# temp.net
KiCad netlist of a schematic drawn in EAGLE
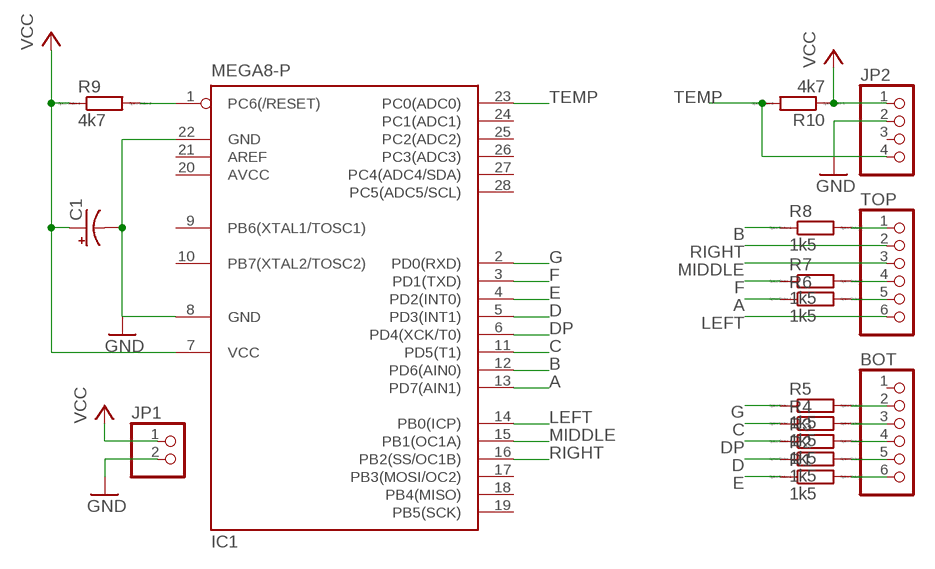
[diagram p0: schematic, sheet 1]

(export (version "E")
  (design (tool "Eeschema 10.0.6"))
  (components
    (comp (ref "BOT")
      (value "PINHD-1X6")
      (footprint "eagle-import:1X06")
      (libsource (lib "eagle-import") (part "PINHD-1X6"))
    )
    (comp (ref "C1")
      (value "CPOL-US153CLV-0505")
      (footprint "eagle-import:153CLV-0505")
      (libsource (lib "eagle-import") (part "CPOL-US153CLV-0505"))
    )
    (comp (ref "IC1")
      (value "MEGA8-P")
      (footprint "eagle-import:DIL28-3")
      (libsource (lib "eagle-import") (part "MEGA8-P"))
    )
    (comp (ref "JP1")
      (value "PINHD-1X2")
      (footprint "eagle-import:1X02")
      (libsource (lib "eagle-import") (part "PINHD-1X2"))
    )
    (comp (ref "JP2")
      (value "PINHD-1X4")
      (footprint "eagle-import:1X04")
      (libsource (lib "eagle-import") (part "PINHD-1X4"))
    )
    (comp (ref "R1")
      (value "1k5")
      (footprint "eagle-import:R1206")
      (libsource (lib "eagle-import") (part "R-EU_R1206"))
    )
    (comp (ref "R2")
      (value "1k5")
      (footprint "eagle-import:R1206")
      (libsource (lib "eagle-import") (part "R-EU_R1206"))
    )
    (comp (ref "R3")
      (value "1k5")
      (footprint "eagle-import:R1206")
      (libsource (lib "eagle-import") (part "R-EU_R1206"))
    )
    (comp (ref "R4")
      (value "1k5")
      (footprint "eagle-import:R1206")
      (libsource (lib "eagle-import") (part "R-EU_R1206"))
    )
    (comp (ref "R5")
      (value "1k5")
      (footprint "eagle-import:R1206")
      (libsource (lib "eagle-import") (part "R-EU_R1206"))
    )
    (comp (ref "R6")
      (value "1k5")
      (footprint "eagle-import:R1206")
      (libsource (lib "eagle-import") (part "R-EU_R1206"))
    )
    (comp (ref "R7")
      (value "1k5")
      (footprint "eagle-import:R1206")
      (libsource (lib "eagle-import") (part "R-EU_R1206"))
    )
    (comp (ref "R8")
      (value "1k5")
      (footprint "eagle-import:R1206")
      (libsource (lib "eagle-import") (part "R-EU_R1206"))
    )
    (comp (ref "R9")
      (value "4k7")
      (footprint "eagle-import:R1206")
      (libsource (lib "eagle-import") (part "R-EU_R1206"))
    )
    (comp (ref "R10")
      (value "4k7")
      (footprint "eagle-import:R1206")
      (libsource (lib "eagle-import") (part "R-EU_R1206"))
    )
    (comp (ref "TOP")
      (value "PINHD-1X6")
      (footprint "eagle-import:1X06")
      (libsource (lib "eagle-import") (part "PINHD-1X6"))
    )
  )
  (nets
    (net (code "1") (name "/A") (class "Default")
      (node (ref "IC1") (pin "13") (pinfunction "PD7(AIN1)_13") (pintype "bidirectional"))
      (node (ref "R6") (pin "1") (pinfunction "1_1") (pintype "passive"))
    )
    (net (code "2") (name "/AVCC") (class "Default")
      (node (ref "IC1") (pin "20") (pinfunction "AVCC_20") (pintype "power_in"))
    )
    (net (code "3") (name "/B") (class "Default")
      (node (ref "IC1") (pin "12") (pinfunction "PD6(AIN0)_12") (pintype "bidirectional"))
      (node (ref "R8") (pin "1") (pinfunction "1_1") (pintype "passive"))
    )
    (net (code "4") (name "/C") (class "Default")
      (node (ref "IC1") (pin "11") (pinfunction "PD5(T1)_11") (pintype "bidirectional"))
      (node (ref "R4") (pin "1") (pinfunction "1_1") (pintype "passive"))
    )
    (net (code "5") (name "/D") (class "Default")
      (node (ref "IC1") (pin "5") (pinfunction "PD3(INT1)_5") (pintype "bidirectional"))
      (node (ref "R2") (pin "1") (pinfunction "1_1") (pintype "passive"))
    )
    (net (code "6") (name "/DP") (class "Default")
      (node (ref "IC1") (pin "6") (pinfunction "PD4(XCK/T0)_6") (pintype "bidirectional"))
      (node (ref "R3") (pin "1") (pinfunction "1_1") (pintype "passive"))
    )
    (net (code "7") (name "/E") (class "Default")
      (node (ref "IC1") (pin "4") (pinfunction "PD2(INT0)_4") (pintype "bidirectional"))
      (node (ref "R1") (pin "1") (pinfunction "1_1") (pintype "passive"))
    )
    (net (code "8") (name "/F") (class "Default")
      (node (ref "IC1") (pin "3") (pinfunction "PD1(TXD)_3") (pintype "bidirectional"))
      (node (ref "R7") (pin "1") (pinfunction "1_1") (pintype "passive"))
    )
    (net (code "9") (name "/G") (class "Default")
      (node (ref "IC1") (pin "2") (pinfunction "PD0(RXD)_2") (pintype "bidirectional"))
      (node (ref "R5") (pin "1") (pinfunction "1_1") (pintype "passive"))
    )
    (net (code "10") (name "/LEFT") (class "Default")
      (node (ref "IC1") (pin "14") (pinfunction "PB0(ICP)_14") (pintype "bidirectional"))
      (node (ref "TOP") (pin "6") (pinfunction "6_6") (pintype "passive"))
    )
    (net (code "11") (name "/MIDDLE") (class "Default")
      (node (ref "IC1") (pin "15") (pinfunction "PB1(OC1A)_15") (pintype "bidirectional"))
      (node (ref "TOP") (pin "3") (pinfunction "3_3") (pintype "passive"))
    )
    (net (code "12") (name "/RIGHT") (class "Default")
      (node (ref "IC1") (pin "16") (pinfunction "PB2(SS/OC1B)_16") (pintype "bidirectional"))
      (node (ref "TOP") (pin "2") (pinfunction "2_2") (pintype "passive"))
    )
    (net (code "13") (name "/TEMP") (class "Default")
      (node (ref "IC1") (pin "23") (pinfunction "PC0(ADC0)_23") (pintype "bidirectional"))
      (node (ref "JP2") (pin "4") (pinfunction "4_4") (pintype "passive"))
      (node (ref "R10") (pin "2") (pinfunction "2_2") (pintype "passive"))
    )
    (net (code "14") (name "GND") (class "Default")
      (node (ref "C1") (pin "-") (pinfunction "-_-") (pintype "passive"))
      (node (ref "IC1") (pin "22") (pinfunction "GND_22") (pintype "power_in"))
      (node (ref "IC1") (pin "8") (pinfunction "GND_8") (pintype "power_in"))
      (node (ref "JP1") (pin "2") (pinfunction "2_2") (pintype "passive"))
      (node (ref "JP2") (pin "2") (pinfunction "2_2") (pintype "passive"))
    )
    (net (code "15") (name "Net-(BOT-Pad2)") (class "Default")
      (node (ref "BOT") (pin "2") (pinfunction "2_2") (pintype "passive"))
      (node (ref "R5") (pin "2") (pinfunction "2_2") (pintype "passive"))
    )
    (net (code "16") (name "Net-(BOT-Pad3)") (class "Default")
      (node (ref "BOT") (pin "3") (pinfunction "3_3") (pintype "passive"))
      (node (ref "R4") (pin "2") (pinfunction "2_2") (pintype "passive"))
    )
    (net (code "17") (name "Net-(BOT-Pad4)") (class "Default")
      (node (ref "BOT") (pin "4") (pinfunction "4_4") (pintype "passive"))
      (node (ref "R3") (pin "2") (pinfunction "2_2") (pintype "passive"))
    )
    (net (code "18") (name "Net-(BOT-Pad5)") (class "Default")
      (node (ref "BOT") (pin "5") (pinfunction "5_5") (pintype "passive"))
      (node (ref "R2") (pin "2") (pinfunction "2_2") (pintype "passive"))
    )
    (net (code "19") (name "Net-(BOT-Pad6)") (class "Default")
      (node (ref "BOT") (pin "6") (pinfunction "6_6") (pintype "passive"))
      (node (ref "R1") (pin "2") (pinfunction "2_2") (pintype "passive"))
    )
    (net (code "20") (name "Net-(IC1-PC6({slash}RESET))") (class "Default")
      (node (ref "IC1") (pin "1") (pinfunction "PC6(/RESET)_1") (pintype "bidirectional"))
      (node (ref "R9") (pin "2") (pinfunction "2_2") (pintype "passive"))
    )
    (net (code "21") (name "Net-(R6-Pad2)") (class "Default")
      (node (ref "R6") (pin "2") (pinfunction "2_2") (pintype "passive"))
      (node (ref "TOP") (pin "5") (pinfunction "5_5") (pintype "passive"))
    )
    (net (code "22") (name "Net-(R7-Pad2)") (class "Default")
      (node (ref "R7") (pin "2") (pinfunction "2_2") (pintype "passive"))
      (node (ref "TOP") (pin "4") (pinfunction "4_4") (pintype "passive"))
    )
    (net (code "23") (name "Net-(R8-Pad2)") (class "Default")
      (node (ref "R8") (pin "2") (pinfunction "2_2") (pintype "passive"))
      (node (ref "TOP") (pin "1") (pinfunction "1_1") (pintype "passive"))
    )
    (net (code "24") (name "VCC") (class "Default")
      (node (ref "C1") (pin "+") (pinfunction "+_+") (pintype "passive"))
      (node (ref "IC1") (pin "7") (pinfunction "VCC_7") (pintype "power_in"))
      (node (ref "JP1") (pin "1") (pinfunction "1_1") (pintype "passive"))
      (node (ref "JP2") (pin "1") (pinfunction "1_1") (pintype "passive"))
      (node (ref "R10") (pin "1") (pinfunction "1_1") (pintype "passive"))
      (node (ref "R9") (pin "1") (pinfunction "1_1") (pintype "passive"))
    )
    (net (code "25") (name "unconnected-(BOT-Pad1)") (class "Default")
      (node (ref "BOT") (pin "1") (pinfunction "1_1") (pintype "passive"))
    )
    (net (code "26") (name "unconnected-(IC1-AREF-Pad21)") (class "Default")
      (node (ref "IC1") (pin "21") (pinfunction "AREF_21") (pintype "passive"))
    )
    (net (code "27") (name "unconnected-(IC1-PB3(MOSI{slash}OC2)-Pad17)") (class "Default")
      (node (ref "IC1") (pin "17") (pinfunction "PB3(MOSI/OC2)_17") (pintype "bidirectional"))
    )
    (net (code "28") (name "unconnected-(IC1-PB4(MISO)-Pad18)") (class "Default")
      (node (ref "IC1") (pin "18") (pinfunction "PB4(MISO)_18") (pintype "bidirectional"))
    )
    (net (code "29") (name "unconnected-(IC1-PB5(SCK)-Pad19)") (class "Default")
      (node (ref "IC1") (pin "19") (pinfunction "PB5(SCK)_19") (pintype "bidirectional"))
    )
    (net (code "30") (name "unconnected-(IC1-PB6(XTAL1{slash}TOSC1)-Pad9)") (class "Default")
      (node (ref "IC1") (pin "9") (pinfunction "PB6(XTAL1/TOSC1)_9") (pintype "bidirectional"))
    )
    (net (code "31") (name "unconnected-(IC1-PB7(XTAL2{slash}TOSC2)-Pad10)") (class "Default")
      (node (ref "IC1") (pin "10") (pinfunction "PB7(XTAL2/TOSC2)_10") (pintype "bidirectional"))
    )
    (net (code "32") (name "unconnected-(IC1-PC1(ADC1)-Pad24)") (class "Default")
      (node (ref "IC1") (pin "24") (pinfunction "PC1(ADC1)_24") (pintype "bidirectional"))
    )
    (net (code "33") (name "unconnected-(IC1-PC2(ADC2)-Pad25)") (class "Default")
      (node (ref "IC1") (pin "25") (pinfunction "PC2(ADC2)_25") (pintype "bidirectional"))
    )
    (net (code "34") (name "unconnected-(IC1-PC3(ADC3)-Pad26)") (class "Default")
      (node (ref "IC1") (pin "26") (pinfunction "PC3(ADC3)_26") (pintype "bidirectional"))
    )
    (net (code "35") (name "unconnected-(IC1-PC4(ADC4{slash}SDA)-Pad27)") (class "Default")
      (node (ref "IC1") (pin "27") (pinfunction "PC4(ADC4/SDA)_27") (pintype "bidirectional"))
    )
    (net (code "36") (name "unconnected-(IC1-PC5(ADC5{slash}SCL)-Pad28)") (class "Default")
      (node (ref "IC1") (pin "28") (pinfunction "PC5(ADC5/SCL)_28") (pintype "bidirectional"))
    )
    (net (code "37") (name "unconnected-(JP2-Pad3)") (class "Default")
      (node (ref "JP2") (pin "3") (pinfunction "3_3") (pintype "passive"))
    )
  )
)
